# MTX_Tap_an_er_V15_Nopoti.net
KiCad netlist of a schematic drawn in EAGLE
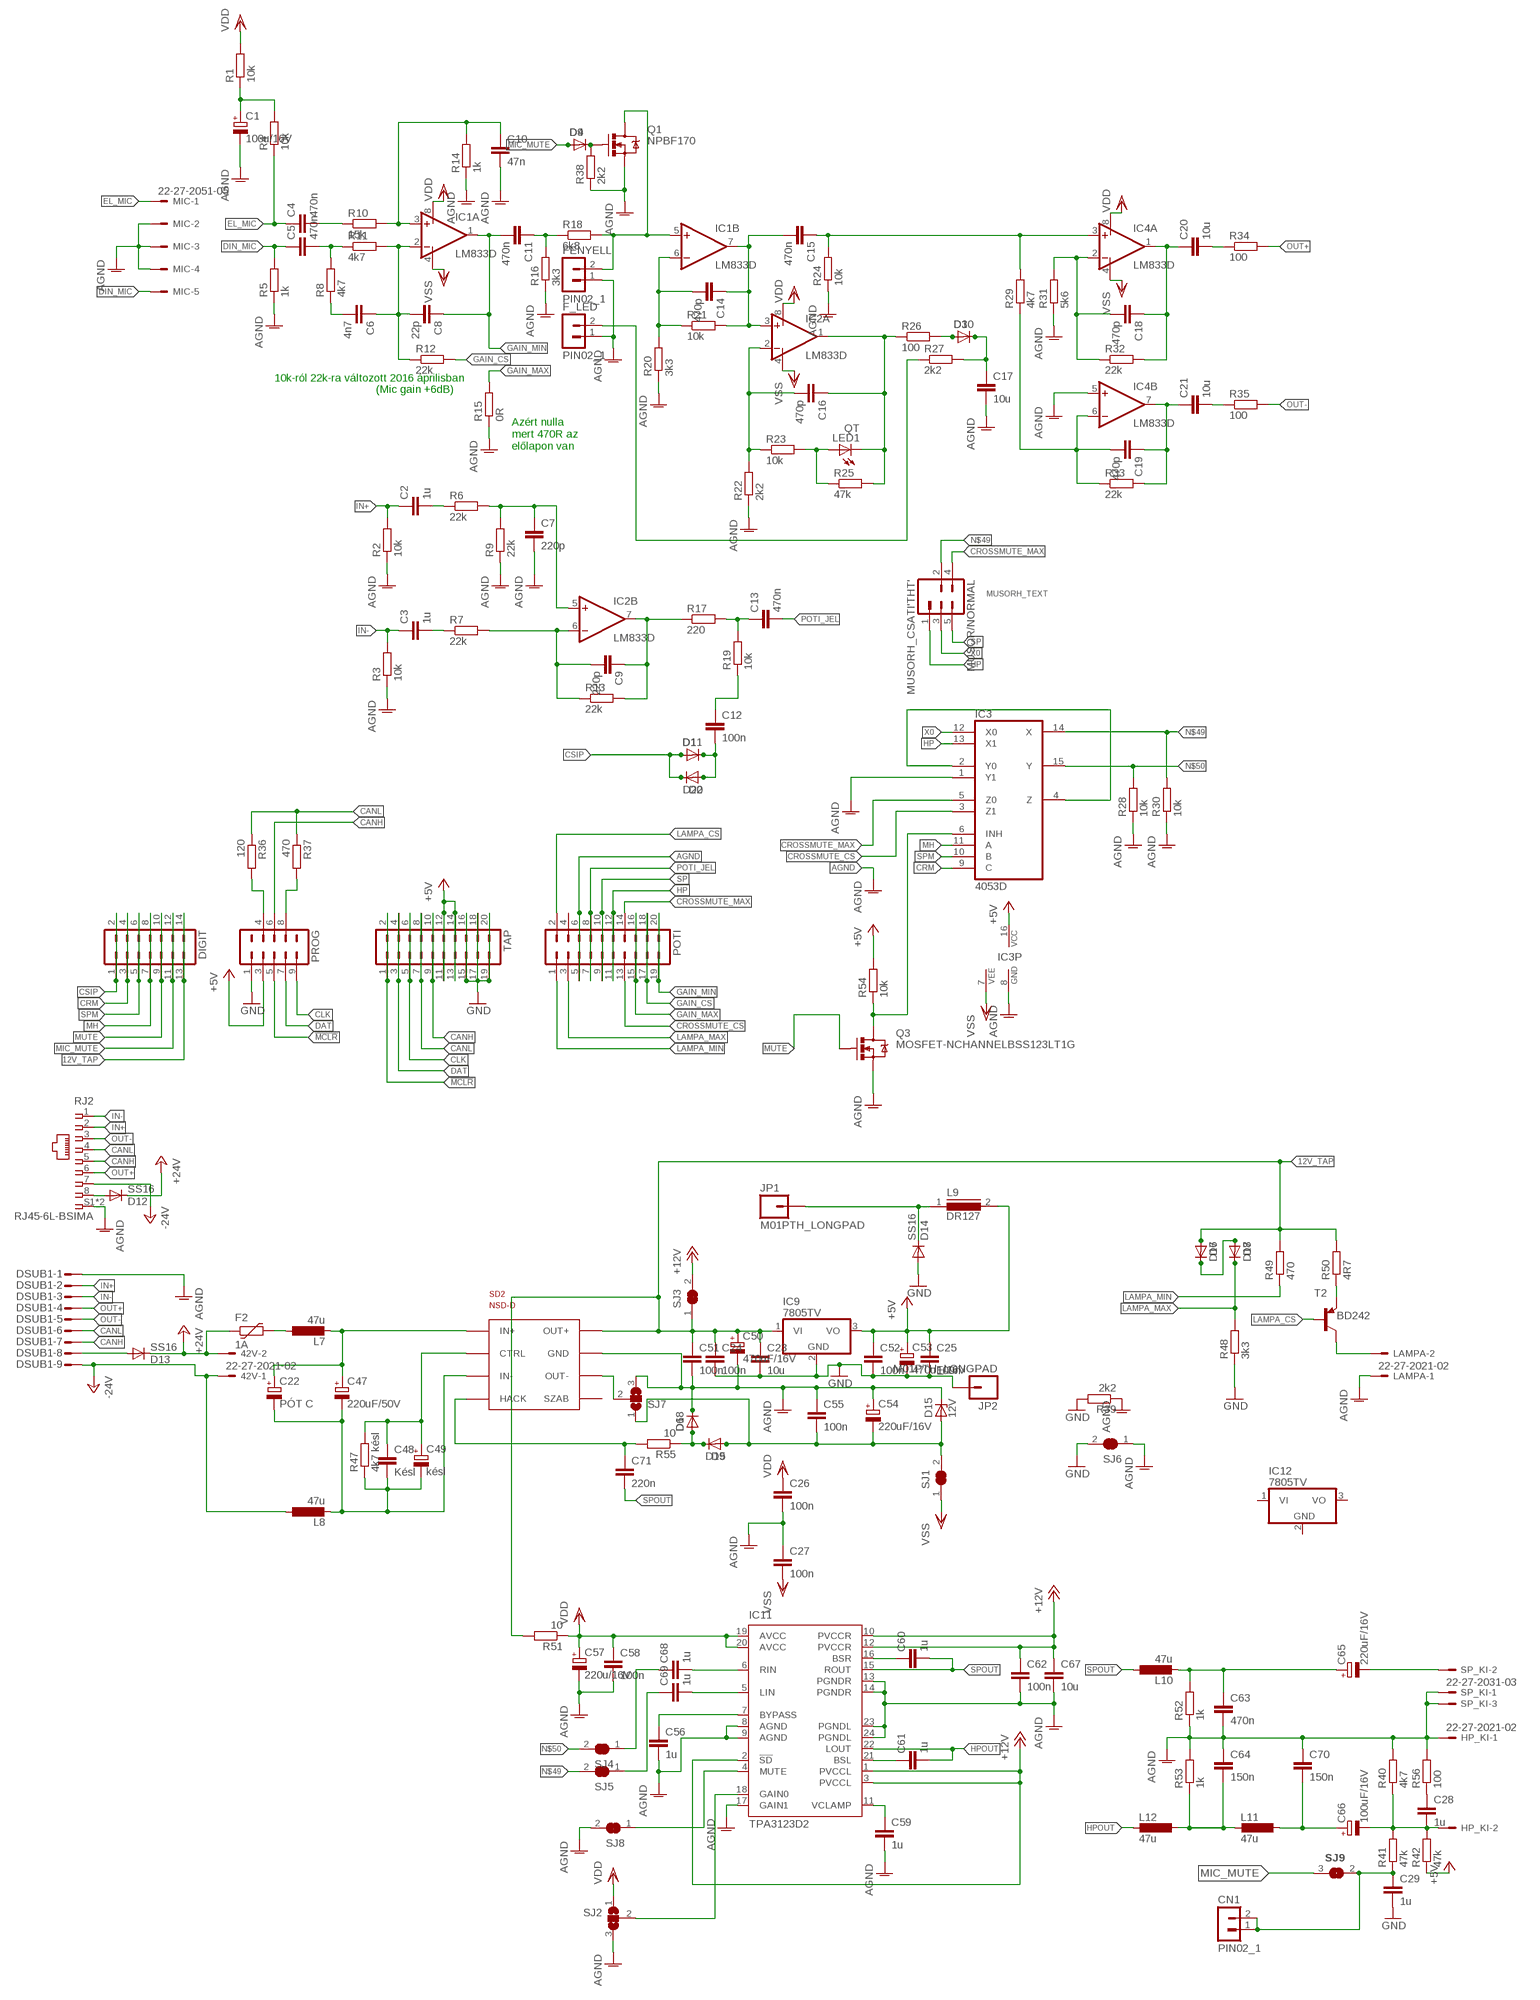
[diagram p0: schematic, sheet 1]

(export (version "E")
  (design (tool "Eeschema 10.0.6"))
  (components
    (comp (ref "42V")
      (value "22-27-2021-02")
      (footprint "eagle-import:6410-02")
      (libsource (lib "eagle-import") (part "22-?-0227-2021"))
    )
    (comp (ref "C1")
      (value "100u/16V")
      (footprint "eagle-import:E2,5-5")
      (libsource (lib "eagle-import") (part "CPOL-EUE2.5-5"))
    )
    (comp (ref "C2")
      (value "1u")
      (footprint "eagle-import:C0805")
      (libsource (lib "eagle-import") (part "C-EUC0805"))
    )
    (comp (ref "C3")
      (value "1u")
      (footprint "eagle-import:C0805")
      (libsource (lib "eagle-import") (part "C-EUC0805"))
    )
    (comp (ref "C4")
      (value "470n")
      (footprint "eagle-import:C0805")
      (libsource (lib "eagle-import") (part "C-EUC0805"))
    )
    (comp (ref "C5")
      (value "470n")
      (footprint "eagle-import:C0805")
      (libsource (lib "eagle-import") (part "C-EUC0805"))
    )
    (comp (ref "C6")
      (value "4n7")
      (footprint "eagle-import:C0805")
      (libsource (lib "eagle-import") (part "C-EUC0805"))
    )
    (comp (ref "C7")
      (value "220p")
      (footprint "eagle-import:C0805")
      (libsource (lib "eagle-import") (part "C-EUC0805"))
    )
    (comp (ref "C8")
      (value "22p")
      (footprint "eagle-import:C0805")
      (libsource (lib "eagle-import") (part "C-EUC0805"))
    )
    (comp (ref "C9")
      (value "220p")
      (footprint "eagle-import:C0805")
      (libsource (lib "eagle-import") (part "C-EUC0805"))
    )
    (comp (ref "C10")
      (value "47n")
      (footprint "eagle-import:C0805")
      (libsource (lib "eagle-import") (part "C-EUC0805"))
    )
    (comp (ref "C11")
      (value "470n")
      (footprint "eagle-import:C0805")
      (libsource (lib "eagle-import") (part "C-EUC0805"))
    )
    (comp (ref "C12")
      (value "100n")
      (footprint "eagle-import:C0805")
      (libsource (lib "eagle-import") (part "C-EUC0805"))
    )
    (comp (ref "C13")
      (value "470n")
      (footprint "eagle-import:C0805")
      (libsource (lib "eagle-import") (part "C-EUC0805"))
    )
    (comp (ref "C14")
      (value "470p")
      (footprint "eagle-import:C0805")
      (libsource (lib "eagle-import") (part "C-EUC0805"))
    )
    (comp (ref "C15")
      (value "470n")
      (footprint "eagle-import:C0805")
      (libsource (lib "eagle-import") (part "C-EUC0805"))
    )
    (comp (ref "C16")
      (value "470p")
      (footprint "eagle-import:C0805")
      (libsource (lib "eagle-import") (part "C-EUC0805"))
    )
    (comp (ref "C17")
      (value "10u")
      (footprint "eagle-import:C0805")
      (libsource (lib "eagle-import") (part "C-EUC0805"))
    )
    (comp (ref "C18")
      (value "470p")
      (footprint "eagle-import:C0805")
      (libsource (lib "eagle-import") (part "C-EUC0805"))
    )
    (comp (ref "C19")
      (value "470p")
      (footprint "eagle-import:C0805")
      (libsource (lib "eagle-import") (part "C-EUC0805"))
    )
    (comp (ref "C20")
      (value "10u")
      (footprint "eagle-import:C0805")
      (libsource (lib "eagle-import") (part "C-EUC0805"))
    )
    (comp (ref "C21")
      (value "10u")
      (footprint "eagle-import:C0805")
      (libsource (lib "eagle-import") (part "C-EUC0805"))
    )
    (comp (ref "C22")
      (value "PÓT C")
      (footprint "eagle-import:E3,5-8")
      (libsource (lib "eagle-import") (part "CPOL-EUE3.5-8"))
    )
    (comp (ref "C23")
      (value "10u")
      (footprint "eagle-import:C0805")
      (libsource (lib "eagle-import") (part "C-EUC0805"))
    )
    (comp (ref "C24")
      (value "100n")
      (footprint "eagle-import:C0805")
      (libsource (lib "eagle-import") (part "C-EUC0805"))
    )
    (comp (ref "C25")
      (value "100n")
      (footprint "eagle-import:C0805")
      (libsource (lib "eagle-import") (part "C-EUC0805"))
    )
    (comp (ref "C26")
      (value "100n")
      (footprint "eagle-import:C0805")
      (libsource (lib "eagle-import") (part "C-EUC0805"))
    )
    (comp (ref "C27")
      (value "100n")
      (footprint "eagle-import:C0805")
      (libsource (lib "eagle-import") (part "C-EUC0805"))
    )
    (comp (ref "C28")
      (value "1u")
      (footprint "eagle-import:C0805")
      (libsource (lib "eagle-import") (part "C-EUC0805"))
    )
    (comp (ref "C29")
      (value "1u")
      (footprint "eagle-import:C0805")
      (libsource (lib "eagle-import") (part "C-EUC0805"))
    )
    (comp (ref "C47")
      (value "220uF/50V")
      (footprint "eagle-import:E3,5-8")
      (libsource (lib "eagle-import") (part "CPOL-EUE3.5-8"))
    )
    (comp (ref "C48")
      (value "Késl")
      (footprint "eagle-import:C0805")
      (libsource (lib "eagle-import") (part "C-EUC0805"))
    )
    (comp (ref "C49")
      (value "késl")
      (footprint "eagle-import:E2,5-5")
      (libsource (lib "eagle-import") (part "CPOL-EUE2.5-5"))
    )
    (comp (ref "C50")
      (value "470uF/16V")
      (footprint "eagle-import:E3,5-8")
      (libsource (lib "eagle-import") (part "CPOL-EUE3.5-8"))
    )
    (comp (ref "C51")
      (value "100n")
      (footprint "eagle-import:C0805")
      (libsource (lib "eagle-import") (part "C-EUC0805"))
    )
    (comp (ref "C52")
      (value "100n")
      (footprint "eagle-import:C0805")
      (libsource (lib "eagle-import") (part "C-EUC0805"))
    )
    (comp (ref "C53")
      (value "470uF/16V")
      (footprint "eagle-import:E3,5-8")
      (libsource (lib "eagle-import") (part "CPOL-EUE3.5-8"))
    )
    (comp (ref "C54")
      (value "220uF/16V")
      (footprint "eagle-import:E2,5-7")
      (libsource (lib "eagle-import") (part "CPOL-EUE2.5-7"))
    )
    (comp (ref "C55")
      (value "100n")
      (footprint "eagle-import:C0805")
      (libsource (lib "eagle-import") (part "C-EUC0805"))
    )
    (comp (ref "C56")
      (value "1u")
      (footprint "eagle-import:C0805")
      (libsource (lib "eagle-import") (part "C-EUC0805"))
    )
    (comp (ref "C57")
      (value "220u/16V")
      (footprint "eagle-import:E2,5-7")
      (libsource (lib "eagle-import") (part "CPOL-EUE2.5-7"))
    )
    (comp (ref "C58")
      (value "100n")
      (footprint "eagle-import:C0805")
      (libsource (lib "eagle-import") (part "C-EUC0805"))
    )
    (comp (ref "C59")
      (value "1u")
      (footprint "eagle-import:C0805")
      (libsource (lib "eagle-import") (part "C-EUC0805"))
    )
    (comp (ref "C60")
      (value "1u")
      (footprint "eagle-import:C0805")
      (libsource (lib "eagle-import") (part "C-EUC0805"))
    )
    (comp (ref "C61")
      (value "1u")
      (footprint "eagle-import:C0805")
      (libsource (lib "eagle-import") (part "C-EUC0805"))
    )
    (comp (ref "C62")
      (value "100n")
      (footprint "eagle-import:C0805")
      (libsource (lib "eagle-import") (part "C-EUC0805"))
    )
    (comp (ref "C63")
      (value "470n")
      (footprint "eagle-import:C0805")
      (libsource (lib "eagle-import") (part "C-EUC0805"))
    )
    (comp (ref "C64")
      (value "150n")
      (footprint "eagle-import:C0805")
      (libsource (lib "eagle-import") (part "C-EUC0805"))
    )
    (comp (ref "C65")
      (value "220uF/16V")
      (footprint "eagle-import:E2,5-7")
      (libsource (lib "eagle-import") (part "CPOL-EUE2.5-7"))
    )
    (comp (ref "C66")
      (value "100uF/16V")
      (footprint "eagle-import:E2,5-6")
      (libsource (lib "eagle-import") (part "CPOL-EUE2.5-6"))
    )
    (comp (ref "C67")
      (value "10u")
      (footprint "eagle-import:C0805")
      (libsource (lib "eagle-import") (part "C-EUC0805"))
    )
    (comp (ref "C68")
      (value "1u")
      (footprint "eagle-import:C0805")
      (libsource (lib "eagle-import") (part "C-EUC0805"))
    )
    (comp (ref "C69")
      (value "1u")
      (footprint "eagle-import:C0805")
      (libsource (lib "eagle-import") (part "C-EUC0805"))
    )
    (comp (ref "C70")
      (value "150n")
      (footprint "eagle-import:C0805")
      (libsource (lib "eagle-import") (part "C-EUC0805"))
    )
    (comp (ref "C71")
      (value "220n")
      (footprint "eagle-import:C0805")
      (libsource (lib "eagle-import") (part "C-EUC0805"))
    )
    (comp (ref "CN1")
      (value "PIN02_1")
      (footprint "eagle-import:PIN02_1")
      (libsource (lib "eagle-import") (part "PIN02_1"))
    )
    (comp (ref "D1")
      (value "1N4148")
      (footprint "eagle-import:DGLASSSMD")
      (libsource (lib "eagle-import") (part "DGLASSMD"))
    )
    (comp (ref "D2")
      (value "1N4148")
      (footprint "eagle-import:DGLASSSMD")
      (libsource (lib "eagle-import") (part "DGLASSMD"))
    )
    (comp (ref "D3")
      (value "1N4148")
      (footprint "eagle-import:DGLASSSMD")
      (libsource (lib "eagle-import") (part "DGLASSMD"))
    )
    (comp (ref "D4")
      (value "1N4148")
      (footprint "eagle-import:DGLASSSMD")
      (libsource (lib "eagle-import") (part "DGLASSMD"))
    )
    (comp (ref "D5")
      (value "D0805")
      (footprint "eagle-import:D0805")
      (libsource (lib "eagle-import") (part "D0805"))
    )
    (comp (ref "D6")
      (value "D0805")
      (footprint "eagle-import:D0805")
      (libsource (lib "eagle-import") (part "D0805"))
    )
    (comp (ref "D7")
      (value "D0805")
      (footprint "eagle-import:D0805")
      (libsource (lib "eagle-import") (part "D0805"))
    )
    (comp (ref "D8")
      (value "D0805")
      (footprint "eagle-import:D0805")
      (libsource (lib "eagle-import") (part "D0805"))
    )
    (comp (ref "D9")
      (value "D0805")
      (footprint "eagle-import:D0805")
      (libsource (lib "eagle-import") (part "D0805"))
    )
    (comp (ref "D10")
      (value "D0805")
      (footprint "eagle-import:D0805")
      (libsource (lib "eagle-import") (part "D0805"))
    )
    (comp (ref "D11")
      (value "D0805")
      (footprint "eagle-import:D0805")
      (libsource (lib "eagle-import") (part "D0805"))
    )
    (comp (ref "D12")
      (value "SS16")
      (footprint "eagle-import:DO-214AC")
      (libsource (lib "eagle-import") (part "DIODE-DO-214AC"))
    )
    (comp (ref "D13")
      (value "SS16")
      (footprint "eagle-import:DO-214AC")
      (libsource (lib "eagle-import") (part "DIODE-DO-214AC"))
    )
    (comp (ref "D14")
      (value "SS16")
      (footprint "eagle-import:DO-214AC")
      (libsource (lib "eagle-import") (part "DIODE-DO-214AC"))
    )
    (comp (ref "D15")
      (value "12V")
      (footprint "eagle-import:SOD80C")
      (libsource (lib "eagle-import") (part "ZENER-DIODESOD80C"))
    )
    (comp (ref "D16")
      (value "1N4148")
      (footprint "eagle-import:DGLASSSMD")
      (libsource (lib "eagle-import") (part "DGLASSMD"))
    )
    (comp (ref "D17")
      (value "1N4148")
      (footprint "eagle-import:DGLASSSMD")
      (libsource (lib "eagle-import") (part "DGLASSMD"))
    )
    (comp (ref "D18")
      (value "1N4148")
      (footprint "eagle-import:DGLASSSMD")
      (libsource (lib "eagle-import") (part "DGLASSMD"))
    )
    (comp (ref "D19")
      (value "1N4148")
      (footprint "eagle-import:DGLASSSMD")
      (libsource (lib "eagle-import") (part "DGLASSMD"))
    )
    (comp (ref "D20")
      (value "D0805")
      (footprint "eagle-import:D0805")
      (libsource (lib "eagle-import") (part "D0805"))
    )
    (comp (ref "DIGIT")
      (value "MA07-2")
      (footprint "eagle-import:MA07-2")
      (libsource (lib "eagle-import") (part "MA07-2"))
    )
    (comp (ref "DSUB1")
      (value "M09-182S")
      (footprint "eagle-import:182-009-MALE")
      (libsource (lib "eagle-import") (part "M09?S-182"))
    )
    (comp (ref "F2")
      (value "1A")
      (footprint "eagle-import:PTC1812L")
      (libsource (lib "eagle-import") (part "FUSE_PTC-1812"))
    )
    (comp (ref "FENYELL")
      (value "PIN02_1")
      (footprint "eagle-import:PIN02_1")
      (libsource (lib "eagle-import") (part "PIN02_1"))
    )
    (comp (ref "F_LED")
      (value "PIN02_1")
      (footprint "eagle-import:PIN02_1")
      (libsource (lib "eagle-import") (part "PIN02_1"))
    )
    (comp (ref "HP_KI")
      (value "22-27-2021-02")
      (footprint "eagle-import:6410-02")
      (libsource (lib "eagle-import") (part "22-?-0227-2021"))
    )
    (comp (ref "IC1")
      (value "LM833D")
      (footprint "eagle-import:SO08")
      (libsource (lib "eagle-import") (part "LM833D"))
    )
    (comp (ref "IC2")
      (value "LM833D")
      (footprint "eagle-import:SO08")
      (libsource (lib "eagle-import") (part "LM833D"))
    )
    (comp (ref "IC3")
      (value "4053D")
      (footprint "eagle-import:SO16")
      (libsource (lib "eagle-import") (part "4053D"))
    )
    (comp (ref "IC4")
      (value "LM833D")
      (footprint "eagle-import:SO08")
      (libsource (lib "eagle-import") (part "LM833D"))
    )
    (comp (ref "IC9")
      (value "7805TV")
      (footprint "eagle-import:TO220V")
      (libsource (lib "eagle-import") (part "78TV05"))
    )
    (comp (ref "IC11")
      (value "TPA3123D2")
      (footprint "eagle-import:PWP-TSSOP24")
      (fields (field (name "MPN") "TPA3123D2PWP"))
      (libsource (lib "eagle-import") (part "TPA3123D2"))
    )
    (comp (ref "IC12")
      (value "7805TV")
      (footprint "eagle-import:TO220V")
      (libsource (lib "eagle-import") (part "78TV05"))
    )
    (comp (ref "JP1")
      (value "M01PTH_LONGPAD")
      (footprint "eagle-import:1X01_LONGPAD")
      (libsource (lib "eagle-import") (part "M01PTH_LONGPAD"))
    )
    (comp (ref "JP2")
      (value "M01PTH_LONGPAD")
      (footprint "eagle-import:1X01_LONGPAD")
      (libsource (lib "eagle-import") (part "M01PTH_LONGPAD"))
    )
    (comp (ref "L7")
      (value "47u")
      (footprint "eagle-import:PIS2816")
      (libsource (lib "eagle-import") (part "L-EUPIS2816"))
    )
    (comp (ref "L8")
      (value "47u")
      (footprint "eagle-import:PIS2816")
      (libsource (lib "eagle-import") (part "L-EUPIS2816"))
    )
    (comp (ref "L9")
      (value "DR127")
      (footprint "eagle-import:DR127")
      (libsource (lib "eagle-import") (part "DR127"))
    )
    (comp (ref "L10")
      (value "47u")
      (footprint "eagle-import:PIS2816")
      (libsource (lib "eagle-import") (part "L-EUPIS2816"))
    )
    (comp (ref "L11")
      (value "47u")
      (footprint "eagle-import:PIS2816")
      (libsource (lib "eagle-import") (part "L-EUPIS2816"))
    )
    (comp (ref "L12")
      (value "47u")
      (footprint "eagle-import:PIS2816")
      (libsource (lib "eagle-import") (part "L-EUPIS2816"))
    )
    (comp (ref "LAMPA")
      (value "22-27-2021-02")
      (footprint "eagle-import:6410-02")
      (libsource (lib "eagle-import") (part "22-?-0227-2021"))
    )
    (comp (ref "LED1")
      (value "QT")
      (footprint "eagle-import:LED3MM")
      (libsource (lib "eagle-import") (part "LED3MM"))
    )
    (comp (ref "MIC")
      (value "22-27-2051-05")
      (footprint "eagle-import:6410-05")
      (libsource (lib "eagle-import") (part "22-?-0527-2051"))
    )
    (comp (ref "MUSOR/NORMAL")
      (value "MUSORH_CSATI'THT'")
      (footprint "eagle-import:MUSORH_CSATI")
      (libsource (lib "eagle-import") (part "MUSORH_CSATI'THT'"))
    )
    (comp (ref "POTI")
      (value "MA10-2")
      (footprint "eagle-import:MA10-2")
      (libsource (lib "eagle-import") (part "MA10-2"))
    )
    (comp (ref "PROG")
      (value "CN_CANTAN")
      (footprint "eagle-import:CN_CANTAN")
      (libsource (lib "eagle-import") (part "CN_CANTAN"))
    )
    (comp (ref "Q1")
      (value "NPBF170")
      (footprint "eagle-import:SOT23")
      (libsource (lib "eagle-import") (part "MOSFET-NCHANNELBSS138"))
    )
    (comp (ref "Q3")
      (value "MOSFET-NCHANNELBSS123LT1G")
      (footprint "eagle-import:SOT23")
      (libsource (lib "eagle-import") (part "MOSFET-NCHANNELBSS123LT1G"))
    )
    (comp (ref "R1")
      (value "10k")
      (footprint "eagle-import:R0805")
      (libsource (lib "eagle-import") (part "R-EU_R0805"))
    )
    (comp (ref "R2")
      (value "10k")
      (footprint "eagle-import:R0805")
      (libsource (lib "eagle-import") (part "R-EU_R0805"))
    )
    (comp (ref "R3")
      (value "10k")
      (footprint "eagle-import:R0805")
      (libsource (lib "eagle-import") (part "R-EU_R0805"))
    )
    (comp (ref "R4")
      (value "10k")
      (footprint "eagle-import:R0805")
      (libsource (lib "eagle-import") (part "R-EU_R0805"))
    )
    (comp (ref "R5")
      (value "1k")
      (footprint "eagle-import:R0805")
      (libsource (lib "eagle-import") (part "R-EU_R0805"))
    )
    (comp (ref "R6")
      (value "22k")
      (footprint "eagle-import:R0805")
      (libsource (lib "eagle-import") (part "R-EU_R0805"))
    )
    (comp (ref "R7")
      (value "22k")
      (footprint "eagle-import:R0805")
      (libsource (lib "eagle-import") (part "R-EU_R0805"))
    )
    (comp (ref "R8")
      (value "4k7")
      (footprint "eagle-import:R0805")
      (libsource (lib "eagle-import") (part "R-EU_R0805"))
    )
    (comp (ref "R9")
      (value "22k")
      (footprint "eagle-import:R0805")
      (libsource (lib "eagle-import") (part "R-EU_R0805"))
    )
    (comp (ref "R10")
      (value "15k")
      (footprint "eagle-import:R0805")
      (libsource (lib "eagle-import") (part "R-EU_R0805"))
    )
    (comp (ref "R11")
      (value "4k7")
      (footprint "eagle-import:R0805")
      (libsource (lib "eagle-import") (part "R-EU_R0805"))
    )
    (comp (ref "R12")
      (value "22k")
      (footprint "eagle-import:R0805")
      (libsource (lib "eagle-import") (part "R-EU_R0805"))
    )
    (comp (ref "R13")
      (value "22k")
      (footprint "eagle-import:R0805")
      (libsource (lib "eagle-import") (part "R-EU_R0805"))
    )
    (comp (ref "R14")
      (value "1k")
      (footprint "eagle-import:R0805")
      (libsource (lib "eagle-import") (part "R-EU_R0805"))
    )
    (comp (ref "R15")
      (value "0R")
      (footprint "eagle-import:R0805")
      (libsource (lib "eagle-import") (part "R-EU_R0805"))
    )
    (comp (ref "R16")
      (value "3k3")
      (footprint "eagle-import:R0805")
      (libsource (lib "eagle-import") (part "R-EU_R0805"))
    )
    (comp (ref "R17")
      (value "220")
      (footprint "eagle-import:R0805")
      (libsource (lib "eagle-import") (part "R-EU_R0805"))
    )
    (comp (ref "R18")
      (value "6k8")
      (footprint "eagle-import:R0805")
      (libsource (lib "eagle-import") (part "R-EU_R0805"))
    )
    (comp (ref "R19")
      (value "10k")
      (footprint "eagle-import:R0805")
      (libsource (lib "eagle-import") (part "R-EU_R0805"))
    )
    (comp (ref "R20")
      (value "3k3")
      (footprint "eagle-import:R0805")
      (libsource (lib "eagle-import") (part "R-EU_R0805"))
    )
    (comp (ref "R21")
      (value "10k")
      (footprint "eagle-import:R0805")
      (libsource (lib "eagle-import") (part "R-EU_R0805"))
    )
    (comp (ref "R22")
      (value "2k2")
      (footprint "eagle-import:R0805")
      (libsource (lib "eagle-import") (part "R-EU_R0805"))
    )
    (comp (ref "R23")
      (value "10k")
      (footprint "eagle-import:R0805")
      (libsource (lib "eagle-import") (part "R-EU_R0805"))
    )
    (comp (ref "R24")
      (value "10k")
      (footprint "eagle-import:R0805")
      (libsource (lib "eagle-import") (part "R-EU_R0805"))
    )
    (comp (ref "R25")
      (value "47k")
      (footprint "eagle-import:R0805")
      (libsource (lib "eagle-import") (part "R-EU_R0805"))
    )
    (comp (ref "R26")
      (value "100")
      (footprint "eagle-import:R0805")
      (libsource (lib "eagle-import") (part "R-EU_R0805"))
    )
    (comp (ref "R27")
      (value "2k2")
      (footprint "eagle-import:R0805")
      (libsource (lib "eagle-import") (part "R-EU_R0805"))
    )
    (comp (ref "R28")
      (value "10k")
      (footprint "eagle-import:R0805")
      (libsource (lib "eagle-import") (part "R-EU_R0805"))
    )
    (comp (ref "R29")
      (value "4k7")
      (footprint "eagle-import:R0805")
      (libsource (lib "eagle-import") (part "R-EU_R0805"))
    )
    (comp (ref "R30")
      (value "10k")
      (footprint "eagle-import:R0805")
      (libsource (lib "eagle-import") (part "R-EU_R0805"))
    )
    (comp (ref "R31")
      (value "5k6")
      (footprint "eagle-import:R0805")
      (libsource (lib "eagle-import") (part "R-EU_R0805"))
    )
    (comp (ref "R32")
      (value "22k")
      (footprint "eagle-import:R0805")
      (libsource (lib "eagle-import") (part "R-EU_R0805"))
    )
    (comp (ref "R33")
      (value "22k")
      (footprint "eagle-import:R0805")
      (libsource (lib "eagle-import") (part "R-EU_R0805"))
    )
    (comp (ref "R34")
      (value "100")
      (footprint "eagle-import:R0805")
      (libsource (lib "eagle-import") (part "R-EU_R0805"))
    )
    (comp (ref "R35")
      (value "100")
      (footprint "eagle-import:R0805")
      (libsource (lib "eagle-import") (part "R-EU_R0805"))
    )
    (comp (ref "R36")
      (value "120")
      (footprint "eagle-import:R0805")
      (libsource (lib "eagle-import") (part "R-EU_R0805"))
    )
    (comp (ref "R37")
      (value "470")
      (footprint "eagle-import:R0805")
      (libsource (lib "eagle-import") (part "R-EU_R0805"))
    )
    (comp (ref "R38")
      (value "2k2")
      (footprint "eagle-import:R0805")
      (libsource (lib "eagle-import") (part "R-EU_R0805"))
    )
    (comp (ref "R39")
      (value "2k2")
      (footprint "eagle-import:R0805")
      (libsource (lib "eagle-import") (part "R-EU_R0805"))
    )
    (comp (ref "R40")
      (value "4k7")
      (footprint "eagle-import:R0805")
      (libsource (lib "eagle-import") (part "R-EU_R0805"))
    )
    (comp (ref "R41")
      (value "47k")
      (footprint "eagle-import:R0805")
      (libsource (lib "eagle-import") (part "R-EU_R0805"))
    )
    (comp (ref "R42")
      (value "47k")
      (footprint "eagle-import:R0805")
      (libsource (lib "eagle-import") (part "R-EU_R0805"))
    )
    (comp (ref "R47")
      (value "4k7 késl")
      (footprint "eagle-import:R0805")
      (libsource (lib "eagle-import") (part "R-EU_R0805"))
    )
    (comp (ref "R48")
      (value "3k3")
      (footprint "eagle-import:R0805")
      (libsource (lib "eagle-import") (part "R-EU_R0805"))
    )
    (comp (ref "R49")
      (value "470")
      (footprint "eagle-import:R0805")
      (libsource (lib "eagle-import") (part "R-EU_R0805"))
    )
    (comp (ref "R50")
      (value "4R7")
      (footprint "eagle-import:R0805")
      (libsource (lib "eagle-import") (part "R-EU_R0805"))
    )
    (comp (ref "R51")
      (value "10")
      (footprint "eagle-import:R1210")
      (libsource (lib "eagle-import") (part "R-EU_R1210"))
    )
    (comp (ref "R52")
      (value "1k")
      (footprint "eagle-import:R0805")
      (libsource (lib "eagle-import") (part "R-EU_R0805"))
    )
    (comp (ref "R53")
      (value "1k")
      (footprint "eagle-import:R0805")
      (libsource (lib "eagle-import") (part "R-EU_R0805"))
    )
    (comp (ref "R54")
      (value "10k")
      (footprint "eagle-import:R0805")
      (libsource (lib "eagle-import") (part "R-EU_R0805"))
    )
    (comp (ref "R55")
      (value "10")
      (footprint "eagle-import:R0805")
      (libsource (lib "eagle-import") (part "R-EU_R0805"))
    )
    (comp (ref "R56")
      (value "100")
      (footprint "eagle-import:R0805")
      (libsource (lib "eagle-import") (part "R-EU_R0805"))
    )
    (comp (ref "RJ2")
      (value "RJ45-6L-BSIMA")
      (footprint "eagle-import:RJ45")
      (fields (field (name "MPN") "RJ45-6L-B"))
      (libsource (lib "eagle-import") (part "RJ45SIMA-6L-B"))
    )
    (comp (ref "SD2")
      (value "NSD-D")
      (footprint "eagle-import:NSD-D")
      (libsource (lib "eagle-import") (part "NSD-D"))
    )
    (comp (ref "SJ1")
      (value "SOLDERJUMPER_CLOSED")
      (footprint "eagle-import:SOLDERJUMPER_CLOSEDWIRE")
      (libsource (lib "eagle-import") (part "SOLDERJUMPER_CLOSED"))
    )
    (comp (ref "SJ2")
      (value "SJ2WW12")
      (footprint "eagle-import:SJ_2W_12")
      (libsource (lib "eagle-import") (part "SJ2WW12"))
    )
    (comp (ref "SJ3")
      (value "SOLDERJUMPER_CLOSED")
      (footprint "eagle-import:SOLDERJUMPER_CLOSEDWIRE")
      (libsource (lib "eagle-import") (part "SOLDERJUMPER_CLOSED"))
    )
    (comp (ref "SJ4")
      (value "SOLDERJUMPER_CLOSED")
      (footprint "eagle-import:SOLDERJUMPER_CLOSEDWIRE")
      (libsource (lib "eagle-import") (part "SOLDERJUMPER_CLOSED"))
    )
    (comp (ref "SJ5")
      (value "SOLDERJUMPER_CLOSED")
      (footprint "eagle-import:SOLDERJUMPER_CLOSEDWIRE")
      (libsource (lib "eagle-import") (part "SOLDERJUMPER_CLOSED"))
    )
    (comp (ref "SJ6")
      (value "SOLDERJUMPER_CLOSED")
      (footprint "eagle-import:SOLDERJUMPER_CLOSEDWIRE")
      (libsource (lib "eagle-import") (part "SOLDERJUMPER_CLOSED"))
    )
    (comp (ref "SJ7")
      (value "SJ2WW23")
      (footprint "eagle-import:SJ_2W_23")
      (libsource (lib "eagle-import") (part "SJ2WW23"))
    )
    (comp (ref "SJ8")
      (value "SOLDERJUMPER_CLOSED")
      (footprint "eagle-import:SOLDERJUMPER_CLOSEDWIRE")
      (libsource (lib "eagle-import") (part "SOLDERJUMPER_CLOSED"))
    )
    (comp (ref "SJ9") (value "SJ") (footprint "eagle-import:SJ") (libsource (lib "eagle-import") (part "SJ")))
    (comp (ref "SP_KI")
      (value "22-27-2031-03")
      (footprint "eagle-import:6410-03")
      (libsource (lib "eagle-import") (part "22-?-0327-2031"))
    )
    (comp (ref "T2")
      (value "BD242")
      (footprint "eagle-import:TO220V")
      (libsource (lib "eagle-import") (part "-PNP-TO220V"))
    )
    (comp (ref "TAP")
      (value "MA10-2")
      (footprint "eagle-import:MA10-2")
      (libsource (lib "eagle-import") (part "MA10-2"))
    )
    (comp (ref "U$1")
      (value "MUSORH_TEXT")
      (footprint "eagle-import:MUSORH_TEXT")
      (libsource (lib "eagle-import") (part "MUSORH_TEXT"))
    )
  )
  (nets
    (net (code "1") (name "+5V") (class "Default")
      (node (ref "C25") (pin "1") (pinfunction "1_1") (pintype "passive"))
      (node (ref "C52") (pin "1") (pinfunction "1_1") (pintype "passive"))
      (node (ref "C53") (pin "+") (pinfunction "+_+") (pintype "passive"))
      (node (ref "IC3") (pin "16") (pinfunction "VCC_16") (pintype "power_in"))
      (node (ref "IC9") (pin "3") (pinfunction "VO_3") (pintype "passive"))
      (node (ref "L9") (pin "2") (pinfunction "2_2") (pintype "passive"))
      (node (ref "PROG") (pin "3") (pinfunction "3_3") (pintype "passive"))
      (node (ref "R42") (pin "1") (pinfunction "1_1") (pintype "passive"))
      (node (ref "R54") (pin "2") (pinfunction "2_2") (pintype "passive"))
      (node (ref "TAP") (pin "11") (pinfunction "11_11") (pintype "passive"))
      (node (ref "TAP") (pin "12") (pinfunction "12_12") (pintype "passive"))
      (node (ref "TAP") (pin "13") (pinfunction "13_13") (pintype "passive"))
      (node (ref "TAP") (pin "14") (pinfunction "14_14") (pintype "passive"))
    )
    (net (code "2") (name "+12V") (class "Default")
      (node (ref "C62") (pin "1") (pinfunction "1_1") (pintype "passive"))
      (node (ref "C67") (pin "1") (pinfunction "1_1") (pintype "passive"))
      (node (ref "IC11") (pin "1") (pinfunction "PVCCL_1") (pintype "input"))
      (node (ref "IC11") (pin "10") (pinfunction "PVCCR_10") (pintype "input"))
      (node (ref "IC11") (pin "12") (pinfunction "PVCCR_12") (pintype "input"))
      (node (ref "IC11") (pin "2") (pinfunction "~{SD}_2") (pintype "input"))
      (node (ref "IC11") (pin "3") (pinfunction "PVCCL_3") (pintype "input"))
      (node (ref "SJ3") (pin "2") (pinfunction "2_2") (pintype "passive"))
    )
    (net (code "3") (name "+24V") (class "Default")
      (node (ref "42V") (pin "2") (pinfunction "S_2") (pintype "passive"))
      (node (ref "D12") (pin "1") (pinfunction "C_1") (pintype "passive"))
      (node (ref "D13") (pin "1") (pinfunction "C_1") (pintype "passive"))
      (node (ref "F2") (pin "1") (pinfunction "1_1") (pintype "passive"))
    )
    (net (code "4") (name "-24V") (class "Default")
      (node (ref "42V") (pin "1") (pinfunction "S_1") (pintype "passive"))
      (node (ref "DSUB1") (pin "9") (pinfunction "M_9") (pintype "passive"))
      (node (ref "L8") (pin "1") (pinfunction "1_1") (pintype "passive"))
      (node (ref "RJ2") (pin "7") (pinfunction "7_7") (pintype "passive"))
    )
    (net (code "5") (name "/~{MCLR}") (class "Default")
      (node (ref "PROG") (pin "5") (pinfunction "5_5") (pintype "passive"))
      (node (ref "TAP") (pin "1") (pinfunction "1_1") (pintype "passive"))
      (node (ref "TAP") (pin "2") (pinfunction "2_2") (pintype "passive"))
    )
    (net (code "6") (name "12V_TAP") (class "Default")
      (node (ref "C23") (pin "1") (pinfunction "1_1") (pintype "passive"))
      (node (ref "C24") (pin "1") (pinfunction "1_1") (pintype "passive"))
      (node (ref "C50") (pin "+") (pinfunction "+_+") (pintype "passive"))
      (node (ref "C51") (pin "1") (pinfunction "1_1") (pintype "passive"))
      (node (ref "D16") (pin "P$1") (pinfunction "A_P$1") (pintype "passive"))
      (node (ref "D7") (pin "1") (pinfunction "A_1") (pintype "passive"))
      (node (ref "DIGIT") (pin "13") (pinfunction "13_13") (pintype "passive"))
      (node (ref "DIGIT") (pin "14") (pinfunction "14_14") (pintype "passive"))
      (node (ref "IC9") (pin "1") (pinfunction "VI_1") (pintype "input"))
      (node (ref "R49") (pin "2") (pinfunction "2_2") (pintype "passive"))
      (node (ref "R50") (pin "2") (pinfunction "2_2") (pintype "passive"))
      (node (ref "R51") (pin "2") (pinfunction "2_2") (pintype "passive"))
      (node (ref "SD2") (pin "OUT+") (pinfunction "OUT+_OUT+") (pintype "bidirectional"))
      (node (ref "SJ3") (pin "1") (pinfunction "1_1") (pintype "passive"))
    )
    (net (code "7") (name "AGND") (class "Default")
      (node (ref "C1") (pin "-") (pinfunction "-_-") (pintype "passive"))
      (node (ref "C10") (pin "2") (pinfunction "2_2") (pintype "passive"))
      (node (ref "C17") (pin "2") (pinfunction "2_2") (pintype "passive"))
      (node (ref "C26") (pin "2") (pinfunction "2_2") (pintype "passive"))
      (node (ref "C27") (pin "1") (pinfunction "1_1") (pintype "passive"))
      (node (ref "C50") (pin "-") (pinfunction "-_-") (pintype "passive"))
      (node (ref "C51") (pin "2") (pinfunction "2_2") (pintype "passive"))
      (node (ref "C54") (pin "+") (pinfunction "+_+") (pintype "passive"))
      (node (ref "C55") (pin "1") (pinfunction "1_1") (pintype "passive"))
      (node (ref "C56") (pin "2") (pinfunction "2_2") (pintype "passive"))
      (node (ref "C57") (pin "-") (pinfunction "-_-") (pintype "passive"))
      (node (ref "C58") (pin "2") (pinfunction "2_2") (pintype "passive"))
      (node (ref "C59") (pin "2") (pinfunction "2_2") (pintype "passive"))
      (node (ref "C62") (pin "2") (pinfunction "2_2") (pintype "passive"))
      (node (ref "C63") (pin "2") (pinfunction "2_2") (pintype "passive"))
      (node (ref "C64") (pin "1") (pinfunction "1_1") (pintype "passive"))
      (node (ref "C67") (pin "2") (pinfunction "2_2") (pintype "passive"))
      (node (ref "C7") (pin "2") (pinfunction "2_2") (pintype "passive"))
      (node (ref "C70") (pin "1") (pinfunction "1_1") (pintype "passive"))
      (node (ref "D15") (pin "C") (pinfunction "C_C") (pintype "passive"))
      (node (ref "D18") (pin "P$2") (pinfunction "C_P$2") (pintype "passive"))
      (node (ref "D6") (pin "2") (pinfunction "C_2") (pintype "passive"))
      (node (ref "DSUB1") (pin "1") (pinfunction "M_1") (pintype "passive"))
      (node (ref "FENYELL") (pin "1") (pinfunction "1_1") (pintype "passive"))
      (node (ref "F_LED") (pin "1") (pinfunction "1_1") (pintype "passive"))
      (node (ref "HP_KI") (pin "1") (pinfunction "S_1") (pintype "passive"))
      (node (ref "IC11") (pin "13") (pinfunction "PGNDR_13") (pintype "input"))
      (node (ref "IC11") (pin "14") (pinfunction "PGNDR_14") (pintype "input"))
      (node (ref "IC11") (pin "17") (pinfunction "GAIN1_17") (pintype "input"))
      (node (ref "IC11") (pin "23") (pinfunction "PGNDL_23") (pintype "input"))
      (node (ref "IC11") (pin "24") (pinfunction "PGNDL_24") (pintype "input"))
      (node (ref "IC11") (pin "8") (pinfunction "AGND_8") (pintype "input"))
      (node (ref "IC11") (pin "9") (pinfunction "AGND_9") (pintype "input"))
      (node (ref "IC3") (pin "1") (pinfunction "Y1_1") (pintype "bidirectional"))
      (node (ref "IC3") (pin "8") (pinfunction "GND_8") (pintype "power_in"))
      (node (ref "IC4") (pin "5") (pinfunction "+IN_5") (pintype "input"))
      (node (ref "LAMPA") (pin "1") (pinfunction "S_1") (pintype "passive"))
      (node (ref "MIC") (pin "2") (pinfunction "S_2") (pintype "passive"))
      (node (ref "MIC") (pin "3") (pinfunction "S_3") (pintype "passive"))
      (node (ref "MIC") (pin "4") (pinfunction "S_4") (pintype "passive"))
      (node (ref "POTI") (pin "5") (pinfunction "5_5") (pintype "passive"))
      (node (ref "POTI") (pin "6") (pinfunction "6_6") (pintype "passive"))
      (node (ref "Q1") (pin "2") (pinfunction "S_2") (pintype "passive"))
      (node (ref "Q3") (pin "2") (pinfunction "S_2") (pintype "passive"))
      (node (ref "R14") (pin "1") (pinfunction "1_1") (pintype "passive"))
      (node (ref "R15") (pin "1") (pinfunction "1_1") (pintype "passive"))
      (node (ref "R16") (pin "1") (pinfunction "1_1") (pintype "passive"))
      (node (ref "R2") (pin "1") (pinfunction "1_1") (pintype "passive"))
      (node (ref "R20") (pin "1") (pinfunction "1_1") (pintype "passive"))
      (node (ref "R22") (pin "1") (pinfunction "1_1") (pintype "passive"))
      (node (ref "R24") (pin "1") (pinfunction "1_1") (pintype "passive"))
      (node (ref "R28") (pin "1") (pinfunction "1_1") (pintype "passive"))
      (node (ref "R3") (pin "1") (pinfunction "1_1") (pintype "passive"))
      (node (ref "R30") (pin "1") (pinfunction "1_1") (pintype "passive"))
      (node (ref "R31") (pin "1") (pinfunction "1_1") (pintype "passive"))
      (node (ref "R38") (pin "1") (pinfunction "1_1") (pintype "passive"))
      (node (ref "R39") (pin "1") (pinfunction "1_1") (pintype "passive"))
      (node (ref "R40") (pin "2") (pinfunction "2_2") (pintype "passive"))
      (node (ref "R5") (pin "1") (pinfunction "1_1") (pintype "passive"))
      (node (ref "R52") (pin "1") (pinfunction "1_1") (pintype "passive"))
      (node (ref "R53") (pin "2") (pinfunction "2_2") (pintype "passive"))
      (node (ref "R56") (pin "2") (pinfunction "2_2") (pintype "passive"))
      (node (ref "R9") (pin "1") (pinfunction "1_1") (pintype "passive"))
      (node (ref "RJ2") (pin "S1") (pinfunction "S_S1") (pintype "passive"))
      (node (ref "RJ2") (pin "S2") (pinfunction "S_S2") (pintype "passive"))
      (node (ref "SD2") (pin "COMMON") (pinfunction "GND_COMMON") (pintype "bidirectional"))
      (node (ref "SJ2") (pin "3") (pinfunction "3_3") (pintype "passive"))
      (node (ref "SJ6") (pin "1") (pinfunction "1_1") (pintype "passive"))
      (node (ref "SJ7") (pin "3") (pinfunction "3_3") (pintype "passive"))
      (node (ref "SJ8") (pin "2") (pinfunction "2_2") (pintype "passive"))
      (node (ref "SP_KI") (pin "1") (pinfunction "S_1") (pintype "passive"))
      (node (ref "SP_KI") (pin "3") (pinfunction "S_3") (pintype "passive"))
    )
    (net (code "8") (name "CANH") (class "Default")
      (node (ref "DSUB1") (pin "7") (pinfunction "M_7") (pintype "passive"))
      (node (ref "PROG") (pin "6") (pinfunction "6_6") (pintype "passive"))
      (node (ref "RJ2") (pin "5") (pinfunction "5_5") (pintype "passive"))
      (node (ref "TAP") (pin "10") (pinfunction "10_10") (pintype "passive"))
      (node (ref "TAP") (pin "9") (pinfunction "9_9") (pintype "passive"))
    )
    (net (code "9") (name "CANL") (class "Default")
      (node (ref "DSUB1") (pin "6") (pinfunction "M_6") (pintype "passive"))
      (node (ref "R36") (pin "1") (pinfunction "1_1") (pintype "passive"))
      (node (ref "R37") (pin "1") (pinfunction "1_1") (pintype "passive"))
      (node (ref "RJ2") (pin "4") (pinfunction "4_4") (pintype "passive"))
      (node (ref "TAP") (pin "7") (pinfunction "7_7") (pintype "passive"))
      (node (ref "TAP") (pin "8") (pinfunction "8_8") (pintype "passive"))
    )
    (net (code "10") (name "CLK") (class "Default")
      (node (ref "PROG") (pin "9") (pinfunction "9_9") (pintype "passive"))
      (node (ref "TAP") (pin "5") (pinfunction "5_5") (pintype "passive"))
      (node (ref "TAP") (pin "6") (pinfunction "6_6") (pintype "passive"))
    )
    (net (code "11") (name "CRM") (class "Default")
      (node (ref "DIGIT") (pin "3") (pinfunction "3_3") (pintype "passive"))
      (node (ref "DIGIT") (pin "4") (pinfunction "4_4") (pintype "passive"))
      (node (ref "IC3") (pin "9") (pinfunction "C_9") (pintype "input"))
    )
    (net (code "12") (name "CROSSMUTE_CS") (class "Default")
      (node (ref "IC3") (pin "3") (pinfunction "Z1_3") (pintype "bidirectional"))
      (node (ref "POTI") (pin "13") (pinfunction "13_13") (pintype "passive"))
    )
    (net (code "13") (name "CROSSMUTE_MAX") (class "Default")
      (node (ref "IC3") (pin "5") (pinfunction "Z0_5") (pintype "bidirectional"))
      (node (ref "MUSOR/NORMAL") (pin "4") (pinfunction "4_4") (pintype "passive"))
      (node (ref "POTI") (pin "14") (pinfunction "14_14") (pintype "passive"))
    )
    (net (code "14") (name "CSIP") (class "Default")
      (node (ref "D1") (pin "P$1") (pinfunction "A_P$1") (pintype "passive"))
      (node (ref "D11") (pin "1") (pinfunction "A_1") (pintype "passive"))
      (node (ref "D2") (pin "P$2") (pinfunction "C_P$2") (pintype "passive"))
      (node (ref "D20") (pin "2") (pinfunction "C_2") (pintype "passive"))
      (node (ref "DIGIT") (pin "1") (pinfunction "1_1") (pintype "passive"))
      (node (ref "DIGIT") (pin "2") (pinfunction "2_2") (pintype "passive"))
    )
    (net (code "15") (name "DAT") (class "Default")
      (node (ref "PROG") (pin "7") (pinfunction "7_7") (pintype "passive"))
      (node (ref "TAP") (pin "3") (pinfunction "3_3") (pintype "passive"))
      (node (ref "TAP") (pin "4") (pinfunction "4_4") (pintype "passive"))
    )
    (net (code "16") (name "DIN_MIC") (class "Default")
      (node (ref "C5") (pin "1") (pinfunction "1_1") (pintype "passive"))
      (node (ref "MIC") (pin "5") (pinfunction "S_5") (pintype "passive"))
      (node (ref "R5") (pin "2") (pinfunction "2_2") (pintype "passive"))
    )
    (net (code "17") (name "EL_MIC") (class "Default")
      (node (ref "C4") (pin "1") (pinfunction "1_1") (pintype "passive"))
      (node (ref "MIC") (pin "1") (pinfunction "S_1") (pintype "passive"))
      (node (ref "R4") (pin "1") (pinfunction "1_1") (pintype "passive"))
    )
    (net (code "18") (name "GAIN_CS") (class "Default")
      (node (ref "POTI") (pin "17") (pinfunction "17_17") (pintype "passive"))
      (node (ref "POTI") (pin "18") (pinfunction "18_18") (pintype "passive"))
      (node (ref "R12") (pin "2") (pinfunction "2_2") (pintype "passive"))
    )
    (net (code "19") (name "GAIN_MAX") (class "Default")
      (node (ref "POTI") (pin "15") (pinfunction "15_15") (pintype "passive"))
      (node (ref "POTI") (pin "16") (pinfunction "16_16") (pintype "passive"))
      (node (ref "R15") (pin "2") (pinfunction "2_2") (pintype "passive"))
    )
    (net (code "20") (name "GAIN_MIN") (class "Default")
      (node (ref "C11") (pin "2") (pinfunction "2_2") (pintype "passive"))
      (node (ref "C8") (pin "1") (pinfunction "1_1") (pintype "passive"))
      (node (ref "IC1") (pin "1") (pinfunction "OUT_1") (pintype "output"))
      (node (ref "POTI") (pin "19") (pinfunction "19_19") (pintype "passive"))
      (node (ref "POTI") (pin "20") (pinfunction "20_20") (pintype "passive"))
    )
    (net (code "21") (name "GND") (class "Default")
      (node (ref "C23") (pin "2") (pinfunction "2_2") (pintype "passive"))
      (node (ref "C24") (pin "2") (pinfunction "2_2") (pintype "passive"))
      (node (ref "C25") (pin "2") (pinfunction "2_2") (pintype "passive"))
      (node (ref "C29") (pin "2") (pinfunction "2_2") (pintype "passive"))
      (node (ref "C52") (pin "2") (pinfunction "2_2") (pintype "passive"))
      (node (ref "C53") (pin "-") (pinfunction "-_-") (pintype "passive"))
      (node (ref "D14") (pin "2") (pinfunction "A_2") (pintype "passive"))
      (node (ref "IC9") (pin "2") (pinfunction "GND_2") (pintype "passive"))
      (node (ref "JP2") (pin "1") (pinfunction "1_1") (pintype "passive"))
      (node (ref "PROG") (pin "1") (pinfunction "1_1") (pintype "passive"))
      (node (ref "R39") (pin "2") (pinfunction "2_2") (pintype "passive"))
      (node (ref "R48") (pin "1") (pinfunction "1_1") (pintype "passive"))
      (node (ref "SJ6") (pin "2") (pinfunction "2_2") (pintype "passive"))
      (node (ref "TAP") (pin "15") (pinfunction "15_15") (pintype "passive"))
      (node (ref "TAP") (pin "16") (pinfunction "16_16") (pintype "passive"))
      (node (ref "TAP") (pin "17") (pinfunction "17_17") (pintype "passive"))
      (node (ref "TAP") (pin "18") (pinfunction "18_18") (pintype "passive"))
      (node (ref "TAP") (pin "19") (pinfunction "19_19") (pintype "passive"))
      (node (ref "TAP") (pin "20") (pinfunction "20_20") (pintype "passive"))
    )
    (net (code "22") (name "HP") (class "Default")
      (node (ref "IC3") (pin "13") (pinfunction "X1_13") (pintype "bidirectional"))
      (node (ref "MUSOR/NORMAL") (pin "1") (pinfunction "1_1") (pintype "passive"))
      (node (ref "POTI") (pin "11") (pinfunction "11_11") (pintype "passive"))
      (node (ref "POTI") (pin "12") (pinfunction "12_12") (pintype "passive"))
    )
    (net (code "23") (name "HPOUT") (class "Default")
      (node (ref "C61") (pin "2") (pinfunction "2_2") (pintype "passive"))
      (node (ref "IC11") (pin "22") (pinfunction "LOUT_22") (pintype "output"))
      (node (ref "L12") (pin "2") (pinfunction "2_2") (pintype "passive"))
    )
    (net (code "24") (name "IN+") (class "Default")
      (node (ref "C2") (pin "1") (pinfunction "1_1") (pintype "passive"))
      (node (ref "DSUB1") (pin "2") (pinfunction "M_2") (pintype "passive"))
      (node (ref "R2") (pin "2") (pinfunction "2_2") (pintype "passive"))
      (node (ref "RJ2") (pin "2") (pinfunction "2_2") (pintype "passive"))
    )
    (net (code "25") (name "IN-") (class "Default")
      (node (ref "C3") (pin "1") (pinfunction "1_1") (pintype "passive"))
      (node (ref "DSUB1") (pin "3") (pinfunction "M_3") (pintype "passive"))
      (node (ref "R3") (pin "2") (pinfunction "2_2") (pintype "passive"))
      (node (ref "RJ2") (pin "1") (pinfunction "1_1") (pintype "passive"))
    )
    (net (code "26") (name "LAMPA_CS") (class "Default")
      (node (ref "POTI") (pin "2") (pinfunction "2_2") (pintype "passive"))
      (node (ref "T2") (pin "1") (pinfunction "B_1") (pintype "passive"))
    )
    (net (code "27") (name "LAMPA_MAX") (class "Default")
      (node (ref "D17") (pin "P$2") (pinfunction "C_P$2") (pintype "passive"))
      (node (ref "D8") (pin "2") (pinfunction "C_2") (pintype "passive"))
      (node (ref "POTI") (pin "3") (pinfunction "3_3") (pintype "passive"))
      (node (ref "R48") (pin "2") (pinfunction "2_2") (pintype "passive"))
    )
    (net (code "28") (name "LAMPA_MIN") (class "Default")
      (node (ref "POTI") (pin "1") (pinfunction "1_1") (pintype "passive"))
      (node (ref "R49") (pin "1") (pinfunction "1_1") (pintype "passive"))
    )
    (net (code "29") (name "MH") (class "Default")
      (node (ref "DIGIT") (pin "7") (pinfunction "7_7") (pintype "passive"))
      (node (ref "DIGIT") (pin "8") (pinfunction "8_8") (pintype "passive"))
      (node (ref "IC3") (pin "11") (pinfunction "A_11") (pintype "input"))
    )
    (net (code "30") (name "MIC_MUTE") (class "Default")
      (node (ref "D4") (pin "P$1") (pinfunction "A_P$1") (pintype "passive"))
      (node (ref "D9") (pin "1") (pinfunction "A_1") (pintype "passive"))
      (node (ref "DIGIT") (pin "11") (pinfunction "11_11") (pintype "passive"))
      (node (ref "DIGIT") (pin "12") (pinfunction "12_12") (pintype "passive"))
      (node (ref "SJ9") (pin "3") (pinfunction "1_3") (pintype "passive"))
    )
    (net (code "31") (name "MUTE") (class "Default")
      (node (ref "DIGIT") (pin "10") (pinfunction "10_10") (pintype "passive"))
      (node (ref "DIGIT") (pin "9") (pinfunction "9_9") (pintype "passive"))
      (node (ref "Q3") (pin "1") (pinfunction "G_1") (pintype "passive"))
    )
    (net (code "32") (name "N$49") (class "Default")
      (node (ref "IC3") (pin "14") (pinfunction "X_14") (pintype "bidirectional"))
      (node (ref "MUSOR/NORMAL") (pin "2") (pinfunction "2_2") (pintype "passive"))
      (node (ref "R30") (pin "2") (pinfunction "2_2") (pintype "passive"))
      (node (ref "SJ5") (pin "2") (pinfunction "2_2") (pintype "passive"))
    )
    (net (code "33") (name "N$50") (class "Default")
      (node (ref "IC3") (pin "15") (pinfunction "Y_15") (pintype "bidirectional"))
      (node (ref "R28") (pin "2") (pinfunction "2_2") (pintype "passive"))
      (node (ref "SJ4") (pin "2") (pinfunction "2_2") (pintype "passive"))
    )
    (net (code "34") (name "Net-(C1-Pad+)") (class "Default")
      (node (ref "C1") (pin "+") (pinfunction "+_+") (pintype "passive"))
      (node (ref "R1") (pin "1") (pinfunction "1_1") (pintype "passive"))
      (node (ref "R4") (pin "2") (pinfunction "2_2") (pintype "passive"))
    )
    (net (code "35") (name "Net-(C2-Pad2)") (class "Default")
      (node (ref "C2") (pin "2") (pinfunction "2_2") (pintype "passive"))
      (node (ref "R6") (pin "1") (pinfunction "1_1") (pintype "passive"))
    )
    (net (code "36") (name "Net-(C3-Pad2)") (class "Default")
      (node (ref "C3") (pin "2") (pinfunction "2_2") (pintype "passive"))
      (node (ref "R7") (pin "1") (pinfunction "1_1") (pintype "passive"))
    )
    (net (code "37") (name "Net-(C4-Pad2)") (class "Default")
      (node (ref "C4") (pin "2") (pinfunction "2_2") (pintype "passive"))
      (node (ref "R10") (pin "1") (pinfunction "1_1") (pintype "passive"))
    )
    (net (code "38") (name "Net-(C5-Pad2)") (class "Default")
      (node (ref "C5") (pin "2") (pinfunction "2_2") (pintype "passive"))
      (node (ref "R11") (pin "1") (pinfunction "1_1") (pintype "passive"))
      (node (ref "R8") (pin "2") (pinfunction "2_2") (pintype "passive"))
    )
    (net (code "39") (name "Net-(C6-Pad2)") (class "Default")
      (node (ref "C6") (pin "2") (pinfunction "2_2") (pintype "passive"))
      (node (ref "R8") (pin "1") (pinfunction "1_1") (pintype "passive"))
    )
    (net (code "40") (name "Net-(C11-Pad1)") (class "Default")
      (node (ref "C11") (pin "1") (pinfunction "1_1") (pintype "passive"))
      (node (ref "R16") (pin "2") (pinfunction "2_2") (pintype "passive"))
      (node (ref "R18") (pin "1") (pinfunction "1_1") (pintype "passive"))
    )
    (net (code "41") (name "Net-(C12-Pad1)") (class "Default")
      (node (ref "C12") (pin "1") (pinfunction "1_1") (pintype "passive"))
      (node (ref "R19") (pin "1") (pinfunction "1_1") (pintype "passive"))
    )
    (net (code "42") (name "Net-(C13-Pad1)") (class "Default")
      (node (ref "C13") (pin "1") (pinfunction "1_1") (pintype "passive"))
      (node (ref "R17") (pin "2") (pinfunction "2_2") (pintype "passive"))
      (node (ref "R19") (pin "2") (pinfunction "2_2") (pintype "passive"))
    )
    (net (code "43") (name "Net-(C20-Pad2)") (class "Default")
      (node (ref "C20") (pin "2") (pinfunction "2_2") (pintype "passive"))
      (node (ref "R34") (pin "1") (pinfunction "1_1") (pintype "passive"))
    )
    (net (code "44") (name "Net-(C21-Pad2)") (class "Default")
      (node (ref "C21") (pin "2") (pinfunction "2_2") (pintype "passive"))
      (node (ref "R35") (pin "1") (pinfunction "1_1") (pintype "passive"))
    )
    (net (code "45") (name "Net-(C28-Pad1)") (class "Default")
      (node (ref "C28") (pin "1") (pinfunction "1_1") (pintype "passive"))
      (node (ref "R56") (pin "1") (pinfunction "1_1") (pintype "passive"))
    )
    (net (code "46") (name "Net-(C29-Pad1)") (class "Default")
      (node (ref "C29") (pin "1") (pinfunction "1_1") (pintype "passive"))
      (node (ref "CN1") (pin "1") (pinfunction "1_1") (pintype "passive"))
      (node (ref "CN1") (pin "2") (pinfunction "2_2") (pintype "passive"))
      (node (ref "R41") (pin "1") (pinfunction "1_1") (pintype "passive"))
      (node (ref "SJ9") (pin "2") (pinfunction "2_2") (pintype "passive"))
    )
    (net (code "47") (name "Net-(C63-Pad1)") (class "Default")
      (node (ref "C63") (pin "1") (pinfunction "1_1") (pintype "passive"))
      (node (ref "C65") (pin "+") (pinfunction "+_+") (pintype "passive"))
      (node (ref "L10") (pin "2") (pinfunction "2_2") (pintype "passive"))
      (node (ref "R52") (pin "2") (pinfunction "2_2") (pintype "passive"))
    )
    (net (code "48") (name "Net-(C64-Pad2)") (class "Default")
      (node (ref "C64") (pin "2") (pinfunction "2_2") (pintype "passive"))
      (node (ref "L11") (pin "2") (pinfunction "2_2") (pintype "passive"))
      (node (ref "L12") (pin "1") (pinfunction "1_1") (pintype "passive"))
      (node (ref "R53") (pin "1") (pinfunction "1_1") (pintype "passive"))
    )
    (net (code "49") (name "Net-(C66-Pad+)") (class "Default")
      (node (ref "C66") (pin "+") (pinfunction "+_+") (pintype "passive"))
      (node (ref "C70") (pin "2") (pinfunction "2_2") (pintype "passive"))
      (node (ref "L11") (pin "1") (pinfunction "1_1") (pintype "passive"))
    )
    (net (code "50") (name "Net-(C68-Pad1)") (class "Default")
      (node (ref "C68") (pin "1") (pinfunction "1_1") (pintype "passive"))
      (node (ref "SJ4") (pin "1") (pinfunction "1_1") (pintype "passive"))
    )
    (net (code "51") (name "Net-(C69-Pad1)") (class "Default")
      (node (ref "C69") (pin "1") (pinfunction "1_1") (pintype "passive"))
      (node (ref "SJ5") (pin "1") (pinfunction "1_1") (pintype "passive"))
    )
    (net (code "52") (name "Net-(C71-Pad1)") (class "Default")
      (node (ref "C71") (pin "1") (pinfunction "1_1") (pintype "passive"))
      (node (ref "R55") (pin "2") (pinfunction "2_2") (pintype "passive"))
      (node (ref "SD2") (pin "HACK") (pinfunction "HACK_HACK") (pintype "bidirectional"))
    )
    (net (code "53") (name "Net-(D1-C)") (class "Default")
      (node (ref "C12") (pin "2") (pinfunction "2_2") (pintype "passive"))
      (node (ref "D1") (pin "P$2") (pinfunction "C_P$2") (pintype "passive"))
      (node (ref "D11") (pin "2") (pinfunction "C_2") (pintype "passive"))
      (node (ref "D2") (pin "P$1") (pinfunction "A_P$1") (pintype "passive"))
      (node (ref "D20") (pin "1") (pinfunction "A_1") (pintype "passive"))
    )
    (net (code "54") (name "Net-(D4-C)") (class "Default")
      (node (ref "D4") (pin "P$2") (pinfunction "C_P$2") (pintype "passive"))
      (node (ref "D9") (pin "2") (pinfunction "C_2") (pintype "passive"))
      (node (ref "Q1") (pin "1") (pinfunction "G_1") (pintype "passive"))
      (node (ref "R38") (pin "2") (pinfunction "2_2") (pintype "passive"))
    )
    (net (code "55") (name "Net-(D10-A)") (class "Default")
      (node (ref "D10") (pin "1") (pinfunction "A_1") (pintype "passive"))
      (node (ref "D3") (pin "P$1") (pinfunction "A_P$1") (pintype "passive"))
      (node (ref "R26") (pin "2") (pinfunction "2_2") (pintype "passive"))
    )
    (net (code "56") (name "Net-(D10-C)") (class "Default")
      (node (ref "C17") (pin "1") (pinfunction "1_1") (pintype "passive"))
      (node (ref "D10") (pin "2") (pinfunction "C_2") (pintype "passive"))
      (node (ref "D3") (pin "P$2") (pinfunction "C_P$2") (pintype "passive"))
      (node (ref "R27") (pin "2") (pinfunction "2_2") (pintype "passive"))
    )
    (net (code "57") (name "Net-(D12-A)") (class "Default")
      (node (ref "D12") (pin "2") (pinfunction "A_2") (pintype "passive"))
      (node (ref "RJ2") (pin "8") (pinfunction "8_8") (pintype "passive"))
    )
    (net (code "58") (name "Net-(D13-A)") (class "Default")
      (node (ref "D13") (pin "2") (pinfunction "A_2") (pintype "passive"))
      (node (ref "DSUB1") (pin "8") (pinfunction "M_8") (pintype "passive"))
    )
    (net (code "59") (name "Net-(D14-C)") (class "Default")
      (node (ref "D14") (pin "1") (pinfunction "C_1") (pintype "passive"))
      (node (ref "JP1") (pin "1") (pinfunction "1_1") (pintype "passive"))
      (node (ref "L9") (pin "1") (pinfunction "1_1") (pintype "passive"))
    )
    (net (code "60") (name "Net-(D16-C)") (class "Default")
      (node (ref "D16") (pin "P$2") (pinfunction "C_P$2") (pintype "passive"))
      (node (ref "D17") (pin "P$1") (pinfunction "A_P$1") (pintype "passive"))
      (node (ref "D7") (pin "2") (pinfunction "C_2") (pintype "passive"))
      (node (ref "D8") (pin "1") (pinfunction "A_1") (pintype "passive"))
    )
    (net (code "61") (name "Net-(D18-A)") (class "Default")
      (node (ref "D18") (pin "P$1") (pinfunction "A_P$1") (pintype "passive"))
      (node (ref "D19") (pin "P$2") (pinfunction "C_P$2") (pintype "passive"))
      (node (ref "D5") (pin "2") (pinfunction "C_2") (pintype "passive"))
      (node (ref "D6") (pin "1") (pinfunction "A_1") (pintype "passive"))
      (node (ref "R55") (pin "1") (pinfunction "1_1") (pintype "passive"))
    )
    (net (code "62") (name "Net-(D19-A)") (class "Default")
      (node (ref "C54") (pin "-") (pinfunction "-_-") (pintype "passive"))
      (node (ref "C55") (pin "2") (pinfunction "2_2") (pintype "passive"))
      (node (ref "D15") (pin "A") (pinfunction "A_A") (pintype "passive"))
      (node (ref "D19") (pin "P$1") (pinfunction "A_P$1") (pintype "passive"))
      (node (ref "D5") (pin "1") (pinfunction "A_1") (pintype "passive"))
      (node (ref "SJ1") (pin "2") (pinfunction "2_2") (pintype "passive"))
      (node (ref "SJ7") (pin "1") (pinfunction "1_1") (pintype "passive"))
    )
    (net (code "63") (name "Net-(F2-Pad2)") (class "Default")
      (node (ref "F2") (pin "2") (pinfunction "2_2") (pintype "passive"))
      (node (ref "L7") (pin "1") (pinfunction "1_1") (pintype "passive"))
    )
    (net (code "64") (name "Net-(F_LED-Pad2)") (class "Default")
      (node (ref "F_LED") (pin "2") (pinfunction "2_2") (pintype "passive"))
      (node (ref "R27") (pin "1") (pinfunction "1_1") (pintype "passive"))
    )
    (net (code "65") (name "Net-(HP_KIB-S)") (class "Default")
      (node (ref "C28") (pin "2") (pinfunction "2_2") (pintype "passive"))
      (node (ref "C66") (pin "-") (pinfunction "-_-") (pintype "passive"))
      (node (ref "HP_KI") (pin "2") (pinfunction "S_2") (pintype "passive"))
      (node (ref "R40") (pin "1") (pinfunction "1_1") (pintype "passive"))
      (node (ref "R41") (pin "2") (pinfunction "2_2") (pintype "passive"))
      (node (ref "R42") (pin "2") (pinfunction "2_2") (pintype "passive"))
    )
    (net (code "66") (name "Net-(IC1A-+IN)") (class "Default")
      (node (ref "C10") (pin "1") (pinfunction "1_1") (pintype "passive"))
      (node (ref "IC1") (pin "3") (pinfunction "+IN_3") (pintype "input"))
      (node (ref "R10") (pin "2") (pinfunction "2_2") (pintype "passive"))
      (node (ref "R14") (pin "2") (pinfunction "2_2") (pintype "passive"))
    )
    (net (code "67") (name "Net-(IC1A--IN)") (class "Default")
      (node (ref "C6") (pin "1") (pinfunction "1_1") (pintype "passive"))
      (node (ref "C8") (pin "2") (pinfunction "2_2") (pintype "passive"))
      (node (ref "IC1") (pin "2") (pinfunction "-IN_2") (pintype "input"))
      (node (ref "R11") (pin "2") (pinfunction "2_2") (pintype "passive"))
      (node (ref "R12") (pin "1") (pinfunction "1_1") (pintype "passive"))
    )
    (net (code "68") (name "Net-(IC1B-+IN)") (class "Default")
      (node (ref "FENYELL") (pin "2") (pinfunction "2_2") (pintype "passive"))
      (node (ref "IC1") (pin "5") (pinfunction "+IN_5") (pintype "input"))
      (node (ref "Q1") (pin "3") (pinfunction "D_3") (pintype "passive"))
      (node (ref "R18") (pin "2") (pinfunction "2_2") (pintype "passive"))
    )
    (net (code "69") (name "Net-(IC1B--IN)") (class "Default")
      (node (ref "C14") (pin "2") (pinfunction "2_2") (pintype "passive"))
      (node (ref "IC1") (pin "6") (pinfunction "-IN_6") (pintype "input"))
      (node (ref "R20") (pin "2") (pinfunction "2_2") (pintype "passive"))
      (node (ref "R21") (pin "1") (pinfunction "1_1") (pintype "passive"))
    )
    (net (code "70") (name "Net-(IC1B-OUT)") (class "Default")
      (node (ref "C14") (pin "1") (pinfunction "1_1") (pintype "passive"))
      (node (ref "C15") (pin "2") (pinfunction "2_2") (pintype "passive"))
      (node (ref "IC1") (pin "7") (pinfunction "OUT_7") (pintype "output"))
      (node (ref "IC2") (pin "3") (pinfunction "+IN_3") (pintype "input"))
      (node (ref "R21") (pin "2") (pinfunction "2_2") (pintype "passive"))
    )
    (net (code "71") (name "Net-(IC2A--IN)") (class "Default")
      (node (ref "C16") (pin "2") (pinfunction "2_2") (pintype "passive"))
      (node (ref "IC2") (pin "2") (pinfunction "-IN_2") (pintype "input"))
      (node (ref "R22") (pin "2") (pinfunction "2_2") (pintype "passive"))
      (node (ref "R23") (pin "1") (pinfunction "1_1") (pintype "passive"))
    )
    (net (code "72") (name "Net-(IC2A-OUT)") (class "Default")
      (node (ref "C16") (pin "1") (pinfunction "1_1") (pintype "passive"))
      (node (ref "IC2") (pin "1") (pinfunction "OUT_1") (pintype "output"))
      (node (ref "LED1") (pin "K") (pinfunction "C_K") (pintype "passive"))
      (node (ref "R25") (pin "2") (pinfunction "2_2") (pintype "passive"))
      (node (ref "R26") (pin "1") (pinfunction "1_1") (pintype "passive"))
    )
    (net (code "73") (name "Net-(IC2B-+IN)") (class "Default")
      (node (ref "C7") (pin "1") (pinfunction "1_1") (pintype "passive"))
      (node (ref "IC2") (pin "5") (pinfunction "+IN_5") (pintype "input"))
      (node (ref "R6") (pin "2") (pinfunction "2_2") (pintype "passive"))
      (node (ref "R9") (pin "2") (pinfunction "2_2") (pintype "passive"))
    )
    (net (code "74") (name "Net-(IC2B--IN)") (class "Default")
      (node (ref "C9") (pin "2") (pinfunction "2_2") (pintype "passive"))
      (node (ref "IC2") (pin "6") (pinfunction "-IN_6") (pintype "input"))
      (node (ref "R13") (pin "1") (pinfunction "1_1") (pintype "passive"))
      (node (ref "R7") (pin "2") (pinfunction "2_2") (pintype "passive"))
    )
    (net (code "75") (name "Net-(IC2B-OUT)") (class "Default")
      (node (ref "C9") (pin "1") (pinfunction "1_1") (pintype "passive"))
      (node (ref "IC2") (pin "7") (pinfunction "OUT_7") (pintype "output"))
      (node (ref "R13") (pin "2") (pinfunction "2_2") (pintype "passive"))
      (node (ref "R17") (pin "1") (pinfunction "1_1") (pintype "passive"))
    )
    (net (code "76") (name "Net-(IC3A-INH)") (class "Default")
      (node (ref "IC3") (pin "6") (pinfunction "INH_6") (pintype "input"))
      (node (ref "Q3") (pin "3") (pinfunction "D_3") (pintype "passive"))
      (node (ref "R54") (pin "1") (pinfunction "1_1") (pintype "passive"))
    )
    (net (code "77") (name "Net-(IC3A-Y0)") (class "Default")
      (node (ref "IC3") (pin "2") (pinfunction "Y0_2") (pintype "bidirectional"))
      (node (ref "IC3") (pin "4") (pinfunction "Z_4") (pintype "bidirectional"))
    )
    (net (code "78") (name "Net-(IC4A-+IN)") (class "Default")
      (node (ref "C15") (pin "1") (pinfunction "1_1") (pintype "passive"))
      (node (ref "IC4") (pin "3") (pinfunction "+IN_3") (pintype "input"))
      (node (ref "R24") (pin "2") (pinfunction "2_2") (pintype "passive"))
      (node (ref "R29") (pin "2") (pinfunction "2_2") (pintype "passive"))
    )
    (net (code "79") (name "Net-(IC4A--IN)") (class "Default")
      (node (ref "C18") (pin "2") (pinfunction "2_2") (pintype "passive"))
      (node (ref "IC4") (pin "2") (pinfunction "-IN_2") (pintype "input"))
      (node (ref "R31") (pin "2") (pinfunction "2_2") (pintype "passive"))
      (node (ref "R32") (pin "1") (pinfunction "1_1") (pintype "passive"))
    )
    (net (code "80") (name "Net-(IC4A-OUT)") (class "Default")
      (node (ref "C18") (pin "1") (pinfunction "1_1") (pintype "passive"))
      (node (ref "C20") (pin "1") (pinfunction "1_1") (pintype "passive"))
      (node (ref "IC4") (pin "1") (pinfunction "OUT_1") (pintype "output"))
      (node (ref "R32") (pin "2") (pinfunction "2_2") (pintype "passive"))
    )
    (net (code "81") (name "Net-(IC4B--IN)") (class "Default")
      (node (ref "C19") (pin "2") (pinfunction "2_2") (pintype "passive"))
      (node (ref "IC4") (pin "6") (pinfunction "-IN_6") (pintype "input"))
      (node (ref "R29") (pin "1") (pinfunction "1_1") (pintype "passive"))
      (node (ref "R33") (pin "1") (pinfunction "1_1") (pintype "passive"))
    )
    (net (code "82") (name "Net-(IC4B-OUT)") (class "Default")
      (node (ref "C19") (pin "1") (pinfunction "1_1") (pintype "passive"))
      (node (ref "C21") (pin "1") (pinfunction "1_1") (pintype "passive"))
      (node (ref "IC4") (pin "7") (pinfunction "OUT_7") (pintype "output"))
      (node (ref "R33") (pin "2") (pinfunction "2_2") (pintype "passive"))
    )
    (net (code "83") (name "Net-(IC11-BSL)") (class "Default")
      (node (ref "C61") (pin "1") (pinfunction "1_1") (pintype "passive"))
      (node (ref "IC11") (pin "21") (pinfunction "BSL_21") (pintype "passive"))
    )
    (net (code "84") (name "Net-(IC11-BSR)") (class "Default")
      (node (ref "C60") (pin "1") (pinfunction "1_1") (pintype "passive"))
      (node (ref "IC11") (pin "16") (pinfunction "BSR_16") (pintype "passive"))
    )
    (net (code "85") (name "Net-(IC11-BYPASS)") (class "Default")
      (node (ref "C56") (pin "1") (pinfunction "1_1") (pintype "passive"))
      (node (ref "IC11") (pin "7") (pinfunction "BYPASS_7") (pintype "input"))
    )
    (net (code "86") (name "Net-(IC11-GAIN0)") (class "Default")
      (node (ref "IC11") (pin "18") (pinfunction "GAIN0_18") (pintype "input"))
      (node (ref "SJ2") (pin "2") (pinfunction "2_2") (pintype "passive"))
    )
    (net (code "87") (name "Net-(IC11-LIN)") (class "Default")
      (node (ref "C69") (pin "2") (pinfunction "2_2") (pintype "passive"))
      (node (ref "IC11") (pin "5") (pinfunction "LIN_5") (pintype "input"))
    )
    (net (code "88") (name "Net-(IC11-MUTE)") (class "Default")
      (node (ref "IC11") (pin "4") (pinfunction "MUTE_4") (pintype "input"))
      (node (ref "SJ8") (pin "1") (pinfunction "1_1") (pintype "passive"))
    )
    (net (code "89") (name "Net-(IC11-RIN)") (class "Default")
      (node (ref "C68") (pin "2") (pinfunction "2_2") (pintype "passive"))
      (node (ref "IC11") (pin "6") (pinfunction "RIN_6") (pintype "input"))
    )
    (net (code "90") (name "Net-(IC11-VCLAMP)") (class "Default")
      (node (ref "C59") (pin "1") (pinfunction "1_1") (pintype "passive"))
      (node (ref "IC11") (pin "11") (pinfunction "VCLAMP_11") (pintype "input"))
    )
    (net (code "91") (name "Net-(LAMPAB-S)") (class "Default")
      (node (ref "LAMPA") (pin "2") (pinfunction "S_2") (pintype "passive"))
      (node (ref "T2") (pin "2") (pinfunction "C_2") (pintype "passive"))
    )
    (net (code "92") (name "Net-(LED1-PadA)") (class "Default")
      (node (ref "LED1") (pin "A") (pinfunction "A_A") (pintype "passive"))
      (node (ref "R23") (pin "2") (pinfunction "2_2") (pintype "passive"))
      (node (ref "R25") (pin "1") (pinfunction "1_1") (pintype "passive"))
    )
    (net (code "93") (name "Net-(PROG-Pad4)") (class "Default")
      (node (ref "PROG") (pin "4") (pinfunction "4_4") (pintype "passive"))
      (node (ref "R36") (pin "2") (pinfunction "2_2") (pintype "passive"))
    )
    (net (code "94") (name "Net-(PROG-Pad8)") (class "Default")
      (node (ref "PROG") (pin "8") (pinfunction "8_8") (pintype "passive"))
      (node (ref "R37") (pin "2") (pinfunction "2_2") (pintype "passive"))
    )
    (net (code "95") (name "Net-(SD2-CTRL)") (class "Default")
      (node (ref "C48") (pin "1") (pinfunction "1_1") (pintype "passive"))
      (node (ref "C49") (pin "+") (pinfunction "+_+") (pintype "passive"))
      (node (ref "R47") (pin "2") (pinfunction "2_2") (pintype "passive"))
      (node (ref "SD2") (pin "CONTROL") (pinfunction "CTRL_CONTROL") (pintype "bidirectional"))
    )
    (net (code "96") (name "Net-(SD2-IN+)") (class "Default")
      (node (ref "C22") (pin "+") (pinfunction "+_+") (pintype "passive"))
      (node (ref "C47") (pin "+") (pinfunction "+_+") (pintype "passive"))
      (node (ref "L7") (pin "2") (pinfunction "2_2") (pintype "passive"))
      (node (ref "SD2") (pin "INPUT+") (pinfunction "IN+_INPUT+") (pintype "bidirectional"))
    )
    (net (code "97") (name "Net-(SD2-IN-)") (class "Default")
      (node (ref "C22") (pin "-") (pinfunction "-_-") (pintype "passive"))
      (node (ref "C47") (pin "-") (pinfunction "-_-") (pintype "passive"))
      (node (ref "C48") (pin "2") (pinfunction "2_2") (pintype "passive"))
      (node (ref "C49") (pin "-") (pinfunction "-_-") (pintype "passive"))
      (node (ref "L8") (pin "2") (pinfunction "2_2") (pintype "passive"))
      (node (ref "R47") (pin "1") (pinfunction "1_1") (pintype "passive"))
      (node (ref "SD2") (pin "INPUT-") (pinfunction "IN-_INPUT-") (pintype "bidirectional"))
    )
    (net (code "98") (name "Net-(SD2-PadOUT-)") (class "Default")
      (node (ref "SD2") (pin "OUT-") (pinfunction "OUT-_OUT-") (pintype "bidirectional"))
      (node (ref "SJ7") (pin "2") (pinfunction "2_2") (pintype "passive"))
    )
    (net (code "99") (name "Net-(SP_KIB-S)") (class "Default")
      (node (ref "C65") (pin "-") (pinfunction "-_-") (pintype "passive"))
      (node (ref "SP_KI") (pin "2") (pinfunction "S_2") (pintype "passive"))
    )
    (net (code "100") (name "Net-(T2-E)") (class "Default")
      (node (ref "R50") (pin "1") (pinfunction "1_1") (pintype "passive"))
      (node (ref "T2") (pin "3") (pinfunction "E_3") (pintype "passive"))
    )
    (net (code "101") (name "OUT+") (class "Default")
      (node (ref "DSUB1") (pin "4") (pinfunction "M_4") (pintype "passive"))
      (node (ref "R34") (pin "2") (pinfunction "2_2") (pintype "passive"))
      (node (ref "RJ2") (pin "6") (pinfunction "6_6") (pintype "passive"))
    )
    (net (code "102") (name "OUT-") (class "Default")
      (node (ref "DSUB1") (pin "5") (pinfunction "M_5") (pintype "passive"))
      (node (ref "R35") (pin "2") (pinfunction "2_2") (pintype "passive"))
      (node (ref "RJ2") (pin "3") (pinfunction "3_3") (pintype "passive"))
    )
    (net (code "103") (name "POTI_JEL") (class "Default")
      (node (ref "C13") (pin "2") (pinfunction "2_2") (pintype "passive"))
      (node (ref "POTI") (pin "7") (pinfunction "7_7") (pintype "passive"))
      (node (ref "POTI") (pin "8") (pinfunction "8_8") (pintype "passive"))
    )
    (net (code "104") (name "SP") (class "Default")
      (node (ref "MUSOR/NORMAL") (pin "5") (pinfunction "5_5") (pintype "passive"))
      (node (ref "POTI") (pin "10") (pinfunction "10_10") (pintype "passive"))
      (node (ref "POTI") (pin "9") (pinfunction "9_9") (pintype "passive"))
    )
    (net (code "105") (name "SPM") (class "Default")
      (node (ref "DIGIT") (pin "5") (pinfunction "5_5") (pintype "passive"))
      (node (ref "DIGIT") (pin "6") (pinfunction "6_6") (pintype "passive"))
      (node (ref "IC3") (pin "10") (pinfunction "B_10") (pintype "input"))
    )
    (net (code "106") (name "SPOUT") (class "Default")
      (node (ref "C60") (pin "2") (pinfunction "2_2") (pintype "passive"))
      (node (ref "C71") (pin "2") (pinfunction "2_2") (pintype "passive"))
      (node (ref "IC11") (pin "15") (pinfunction "ROUT_15") (pintype "output"))
      (node (ref "L10") (pin "1") (pinfunction "1_1") (pintype "passive"))
    )
    (net (code "107") (name "VDD") (class "Default")
      (node (ref "C26") (pin "1") (pinfunction "1_1") (pintype "passive"))
      (node (ref "C57") (pin "+") (pinfunction "+_+") (pintype "passive"))
      (node (ref "C58") (pin "1") (pinfunction "1_1") (pintype "passive"))
      (node (ref "IC1") (pin "8") (pinfunction "V+_8") (pintype "power_in"))
      (node (ref "IC11") (pin "19") (pinfunction "AVCC_19") (pintype "input"))
      (node (ref "IC11") (pin "20") (pinfunction "AVCC_20") (pintype "input"))
      (node (ref "IC2") (pin "8") (pinfunction "V+_8") (pintype "power_in"))
      (node (ref "IC4") (pin "8") (pinfunction "V+_8") (pintype "power_in"))
      (node (ref "R1") (pin "2") (pinfunction "2_2") (pintype "passive"))
      (node (ref "R51") (pin "1") (pinfunction "1_1") (pintype "passive"))
      (node (ref "SJ2") (pin "1") (pinfunction "1_1") (pintype "passive"))
    )
    (net (code "108") (name "VSS") (class "Default")
      (node (ref "C27") (pin "2") (pinfunction "2_2") (pintype "passive"))
      (node (ref "IC1") (pin "4") (pinfunction "V-_4") (pintype "power_in"))
      (node (ref "IC2") (pin "4") (pinfunction "V-_4") (pintype "power_in"))
      (node (ref "IC3") (pin "7") (pinfunction "VEE_7") (pintype "power_in"))
      (node (ref "IC4") (pin "4") (pinfunction "V-_4") (pintype "power_in"))
      (node (ref "SJ1") (pin "1") (pinfunction "1_1") (pintype "passive"))
    )
    (net (code "109") (name "X0") (class "Default")
      (node (ref "IC3") (pin "12") (pinfunction "X0_12") (pintype "bidirectional"))
      (node (ref "MUSOR/NORMAL") (pin "3") (pinfunction "3_3") (pintype "passive"))
    )
    (net (code "110") (name "unconnected-(IC12-GND-Pad2)") (class "Default")
      (node (ref "IC12") (pin "2") (pinfunction "GND_2") (pintype "passive"))
    )
    (net (code "111") (name "unconnected-(IC12-VI-Pad1)") (class "Default")
      (node (ref "IC12") (pin "1") (pinfunction "VI_1") (pintype "input"))
    )
    (net (code "112") (name "unconnected-(IC12-VO-Pad3)") (class "Default")
      (node (ref "IC12") (pin "3") (pinfunction "VO_3") (pintype "passive"))
    )
    (net (code "113") (name "unconnected-(POTI-Pad4)") (class "Default")
      (node (ref "POTI") (pin "4") (pinfunction "4_4") (pintype "passive"))
    )
    (net (code "114") (name "unconnected-(SD2-PadSZAB)") (class "Default")
      (node (ref "SD2") (pin "SZAB") (pinfunction "SZAB_SZAB") (pintype "bidirectional"))
    )
  )
)
